# pie-shield.net
KiCad netlist of a schematic drawn in EAGLE
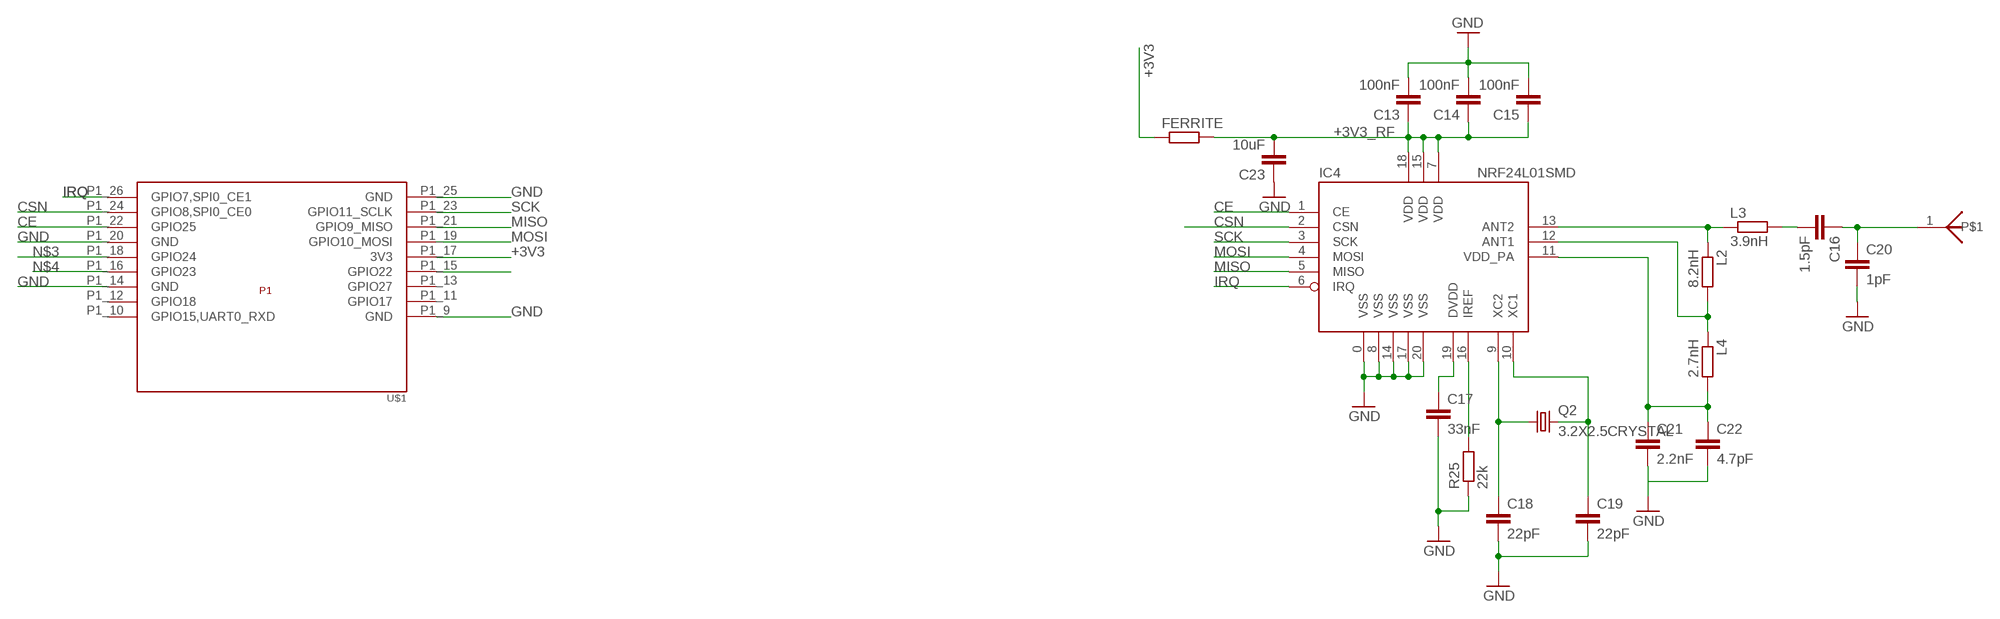
[diagram p0: schematic, sheet 1]

(export (version "E")
  (design (tool "Eeschema 10.0.6"))
  (components
    (comp (ref "ANT")
      (value "CHIPANTENNA")
      (footprint "eagle-import:CHIPANTENNA")
      (libsource (lib "eagle-import") (part "CHIPANTENNA"))
    )
    (comp (ref "C13")
      (value "100nF")
      (footprint "eagle-import:C0402K")
      (libsource (lib "eagle-import") (part "C-EUC0402K"))
    )
    (comp (ref "C14")
      (value "100nF")
      (footprint "eagle-import:C0402K")
      (libsource (lib "eagle-import") (part "C-EUC0402K"))
    )
    (comp (ref "C15")
      (value "100nF")
      (footprint "eagle-import:C0402K")
      (libsource (lib "eagle-import") (part "C-EUC0402K"))
    )
    (comp (ref "C16")
      (value "1.5pF")
      (footprint "eagle-import:C0402K")
      (libsource (lib "eagle-import") (part "C-EUC0402K"))
    )
    (comp (ref "C17")
      (value "33nF")
      (footprint "eagle-import:C0402K")
      (libsource (lib "eagle-import") (part "C-EUC0402K"))
    )
    (comp (ref "C18")
      (value "22pF")
      (footprint "eagle-import:C0402K")
      (libsource (lib "eagle-import") (part "C-EUC0402K"))
    )
    (comp (ref "C19")
      (value "22pF")
      (footprint "eagle-import:C0402K")
      (libsource (lib "eagle-import") (part "C-EUC0402K"))
    )
    (comp (ref "C20")
      (value "1pF")
      (footprint "eagle-import:C0402K")
      (libsource (lib "eagle-import") (part "C-EUC0402K"))
    )
    (comp (ref "C21")
      (value "2.2nF")
      (footprint "eagle-import:C0402K")
      (libsource (lib "eagle-import") (part "C-EUC0402K"))
    )
    (comp (ref "C22")
      (value "4.7pF")
      (footprint "eagle-import:C0402K")
      (libsource (lib "eagle-import") (part "C-EUC0402K"))
    )
    (comp (ref "C23")
      (value "10uF")
      (footprint "eagle-import:C0805K")
      (libsource (lib "eagle-import") (part "C-EUC0805K"))
    )
    (comp (ref "FERRITE")
      (value "R-EU_R0805")
      (footprint "eagle-import:R0805")
      (libsource (lib "eagle-import") (part "R-EU_R0805"))
    )
    (comp (ref "IC4")
      (value "NRF24L01SMD")
      (footprint "eagle-import:QFN20")
      (libsource (lib "eagle-import") (part "NRF24L01SMD"))
    )
    (comp (ref "L2")
      (value "8.2nH")
      (footprint "eagle-import:R0402")
      (libsource (lib "eagle-import") (part "R-EU_R0402"))
    )
    (comp (ref "L3")
      (value "3.9nH")
      (footprint "eagle-import:R0402")
      (libsource (lib "eagle-import") (part "R-EU_R0402"))
    )
    (comp (ref "L4")
      (value "2.7nH")
      (footprint "eagle-import:R0402")
      (libsource (lib "eagle-import") (part "R-EU_R0402"))
    )
    (comp (ref "Q2")
      (value "3.2X2.5CRYSTAL")
      (footprint "eagle-import:CRYSTAL3.2X2.5")
      (libsource (lib "eagle-import") (part "3.2X2.5CRYSTAL"))
    )
    (comp (ref "R25")
      (value "22k")
      (footprint "eagle-import:R0603")
      (libsource (lib "eagle-import") (part "R-EU_R0603"))
    )
    (comp (ref "U$1")
      (value "RASPBERRY-PI_REV2")
      (footprint "eagle-import:RASPBERRY-PI_REV2")
      (libsource (lib "eagle-import") (part "RASPBERRY-PI_REV2"))
    )
  )
  (nets
    (net (code "1") (name "/+3V3") (class "Default")
      (node (ref "FERRITE") (pin "1") (pinfunction "1_1") (pintype "passive"))
      (node (ref "U$1") (pin "P1_17") (pinfunction "3V3_P1_17") (pintype "bidirectional"))
    )
    (net (code "2") (name "/+3V3_RF") (class "Default")
      (node (ref "C13") (pin "1") (pinfunction "1_1") (pintype "passive"))
      (node (ref "C14") (pin "1") (pinfunction "1_1") (pintype "passive"))
      (node (ref "C15") (pin "1") (pinfunction "1_1") (pintype "passive"))
      (node (ref "C23") (pin "2") (pinfunction "2_2") (pintype "passive"))
      (node (ref "FERRITE") (pin "2") (pinfunction "2_2") (pintype "passive"))
      (node (ref "IC4") (pin "15") (pinfunction "VDD_15") (pintype "power_in"))
      (node (ref "IC4") (pin "18") (pinfunction "VDD_18") (pintype "power_in"))
      (node (ref "IC4") (pin "7") (pinfunction "VDD_7") (pintype "power_in"))
    )
    (net (code "3") (name "/CE") (class "Default")
      (node (ref "IC4") (pin "1") (pinfunction "CE_1") (pintype "input"))
      (node (ref "U$1") (pin "P1_22") (pinfunction "GPIO25_P1_22") (pintype "bidirectional"))
    )
    (net (code "4") (name "/CSN") (class "Default")
      (node (ref "IC4") (pin "2") (pinfunction "CSN_2") (pintype "input"))
      (node (ref "U$1") (pin "P1_24") (pinfunction "GPIO8,SPI0_CE0_P1_24") (pintype "bidirectional"))
    )
    (net (code "5") (name "/IRQ") (class "Default")
      (node (ref "IC4") (pin "6") (pinfunction "IRQ_6") (pintype "output"))
      (node (ref "U$1") (pin "P1_26") (pinfunction "GPIO7,SPI0_CE1_P1_26") (pintype "bidirectional"))
    )
    (net (code "6") (name "/MISO") (class "Default")
      (node (ref "IC4") (pin "5") (pinfunction "MISO_5") (pintype "output"))
      (node (ref "U$1") (pin "P1_21") (pinfunction "GPIO9_MISO_P1_21") (pintype "bidirectional"))
    )
    (net (code "7") (name "/MOSI") (class "Default")
      (node (ref "IC4") (pin "4") (pinfunction "MOSI_4") (pintype "input"))
      (node (ref "U$1") (pin "P1_19") (pinfunction "GPIO10_MOSI_P1_19") (pintype "bidirectional"))
    )
    (net (code "8") (name "/N$3") (class "Default")
      (node (ref "U$1") (pin "P1_18") (pinfunction "GPIO24_P1_18") (pintype "bidirectional"))
    )
    (net (code "9") (name "/N$4") (class "Default")
      (node (ref "U$1") (pin "P1_16") (pinfunction "GPIO23_P1_16") (pintype "bidirectional"))
    )
    (net (code "10") (name "/SCK") (class "Default")
      (node (ref "IC4") (pin "3") (pinfunction "SCK_3") (pintype "input"))
      (node (ref "U$1") (pin "P1_23") (pinfunction "GPIO11_SCLK_P1_23") (pintype "bidirectional"))
    )
    (net (code "11") (name "GND") (class "Default")
      (node (ref "C13") (pin "2") (pinfunction "2_2") (pintype "passive"))
      (node (ref "C14") (pin "2") (pinfunction "2_2") (pintype "passive"))
      (node (ref "C15") (pin "2") (pinfunction "2_2") (pintype "passive"))
      (node (ref "C17") (pin "2") (pinfunction "2_2") (pintype "passive"))
      (node (ref "C18") (pin "2") (pinfunction "2_2") (pintype "passive"))
      (node (ref "C19") (pin "2") (pinfunction "2_2") (pintype "passive"))
      (node (ref "C20") (pin "2") (pinfunction "2_2") (pintype "passive"))
      (node (ref "C21") (pin "2") (pinfunction "2_2") (pintype "passive"))
      (node (ref "C22") (pin "2") (pinfunction "2_2") (pintype "passive"))
      (node (ref "C23") (pin "1") (pinfunction "1_1") (pintype "passive"))
      (node (ref "IC4") (pin "0") (pinfunction "VSS_0") (pintype "power_in"))
      (node (ref "IC4") (pin "14") (pinfunction "VSS_14") (pintype "power_in"))
      (node (ref "IC4") (pin "17") (pinfunction "VSS_17") (pintype "power_in"))
      (node (ref "IC4") (pin "20") (pinfunction "VSS_20") (pintype "power_in"))
      (node (ref "IC4") (pin "8") (pinfunction "VSS_8") (pintype "power_in"))
      (node (ref "R25") (pin "1") (pinfunction "1_1") (pintype "passive"))
      (node (ref "U$1") (pin "P1_14") (pinfunction "GND_P1_14") (pintype "bidirectional"))
      (node (ref "U$1") (pin "P1_20") (pinfunction "GND_P1_20") (pintype "bidirectional"))
      (node (ref "U$1") (pin "P1_25") (pinfunction "GND_P1_25") (pintype "bidirectional"))
      (node (ref "U$1") (pin "P1_9") (pinfunction "GND_P1_9") (pintype "bidirectional"))
    )
    (net (code "12") (name "Net-(ANT-P$1)") (class "Default")
      (node (ref "ANT") (pin "1") (pinfunction "P$1_1") (pintype "bidirectional"))
      (node (ref "C16") (pin "1") (pinfunction "1_1") (pintype "passive"))
      (node (ref "C20") (pin "1") (pinfunction "1_1") (pintype "passive"))
    )
    (net (code "13") (name "Net-(C16-Pad2)") (class "Default")
      (node (ref "C16") (pin "2") (pinfunction "2_2") (pintype "passive"))
      (node (ref "L3") (pin "2") (pinfunction "2_2") (pintype "passive"))
    )
    (net (code "14") (name "Net-(IC4-ANT1)") (class "Default")
      (node (ref "IC4") (pin "12") (pinfunction "ANT1_12") (pintype "output"))
      (node (ref "L2") (pin "2") (pinfunction "2_2") (pintype "passive"))
      (node (ref "L4") (pin "1") (pinfunction "1_1") (pintype "passive"))
    )
    (net (code "15") (name "Net-(IC4-ANT2)") (class "Default")
      (node (ref "IC4") (pin "13") (pinfunction "ANT2_13") (pintype "output"))
      (node (ref "L2") (pin "1") (pinfunction "1_1") (pintype "passive"))
      (node (ref "L3") (pin "1") (pinfunction "1_1") (pintype "passive"))
    )
    (net (code "16") (name "Net-(IC4-DVDD)") (class "Default")
      (node (ref "C17") (pin "1") (pinfunction "1_1") (pintype "passive"))
      (node (ref "IC4") (pin "19") (pinfunction "DVDD_19") (pintype "power_in"))
    )
    (net (code "17") (name "Net-(IC4-IREF)") (class "Default")
      (node (ref "IC4") (pin "16") (pinfunction "IREF_16") (pintype "input"))
      (node (ref "R25") (pin "2") (pinfunction "2_2") (pintype "passive"))
    )
    (net (code "18") (name "Net-(IC4-VDD_PA)") (class "Default")
      (node (ref "C21") (pin "1") (pinfunction "1_1") (pintype "passive"))
      (node (ref "C22") (pin "1") (pinfunction "1_1") (pintype "passive"))
      (node (ref "IC4") (pin "11") (pinfunction "VDD_PA_11") (pintype "power_in"))
      (node (ref "L4") (pin "2") (pinfunction "2_2") (pintype "passive"))
    )
    (net (code "19") (name "Net-(IC4-XC1)") (class "Default")
      (node (ref "C19") (pin "1") (pinfunction "1_1") (pintype "passive"))
      (node (ref "IC4") (pin "10") (pinfunction "XC1_10") (pintype "input"))
      (node (ref "Q2") (pin "3") (pinfunction "2_3") (pintype "passive"))
    )
    (net (code "20") (name "Net-(IC4-XC2)") (class "Default")
      (node (ref "C18") (pin "1") (pinfunction "1_1") (pintype "passive"))
      (node (ref "IC4") (pin "9") (pinfunction "XC2_9") (pintype "input"))
      (node (ref "Q2") (pin "1") (pinfunction "1_1") (pintype "passive"))
    )
    (net (code "21") (name "unconnected-(U$1-GPIO15,UART0_RXD-PadP1_10)") (class "Default")
      (node (ref "U$1") (pin "P1_10") (pinfunction "GPIO15,UART0_RXD_P1_10") (pintype "bidirectional"))
    )
    (net (code "22") (name "unconnected-(U$1-GPIO17-PadP1_11)") (class "Default")
      (node (ref "U$1") (pin "P1_11") (pinfunction "GPIO17_P1_11") (pintype "bidirectional"))
    )
    (net (code "23") (name "unconnected-(U$1-GPIO18-PadP1_12)") (class "Default")
      (node (ref "U$1") (pin "P1_12") (pinfunction "GPIO18_P1_12") (pintype "bidirectional"))
    )
    (net (code "24") (name "unconnected-(U$1-GPIO22-PadP1_15)") (class "Default")
      (node (ref "U$1") (pin "P1_15") (pinfunction "GPIO22_P1_15") (pintype "bidirectional"))
    )
    (net (code "25") (name "unconnected-(U$1-GPIO27-PadP1_13)") (class "Default")
      (node (ref "U$1") (pin "P1_13") (pinfunction "GPIO27_P1_13") (pintype "bidirectional"))
    )
  )
)
